# SUB-UNIT.net
KiCad netlist of a schematic drawn in EAGLE
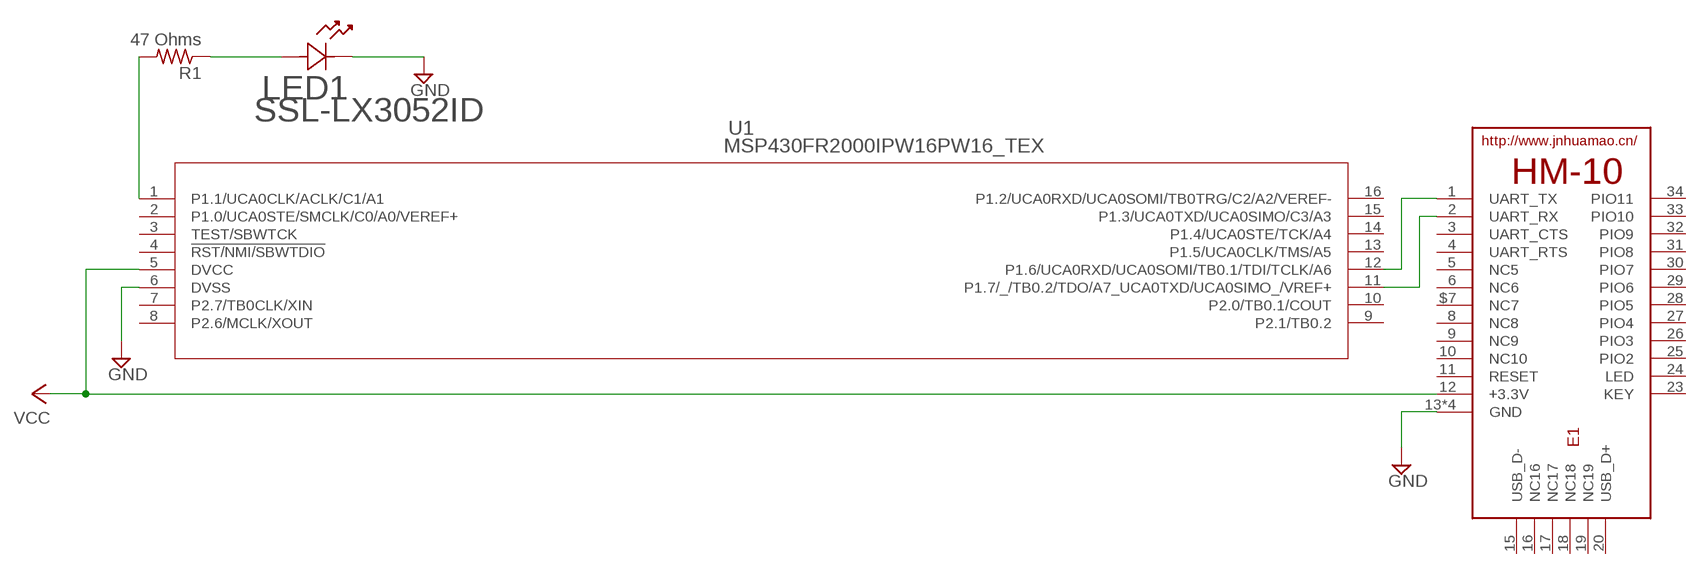
[diagram p0: schematic, sheet 1]

(export (version "E")
  (design (tool "Eeschema 10.0.6"))
  (components
    (comp (ref "E1")
      (value "HM-10-BOARD")
      (footprint "eagle-import:26.9X13X2.2_BOARD")
      (fields (field (name "MF") "Jinan Huamao Technology") (field (name "MP") "HM-10"))
      (libsource (lib "eagle-import") (part "HM-10-BOARD"))
    )
    (comp (ref "LED1")
      (value "SSL-LX3052ID")
      (footprint "eagle-import:LED_SSL-LX30_T-3_LUM")
      (fields (field (name "COPYRIGHT") "Copyright (C) 2023 Ultra Librarian. All rights reserved."))
      (libsource (lib "eagle-import") (part "SSL-LX3052ID"))
    )
    (comp (ref "R1")
      (value "47 Ohms")
      (footprint "eagle-import:0204_5")
      (libsource (lib "eagle-import") (part "R-US_0204/5"))
    )
    (comp (ref "U1")
      (value "MSP430FR2000IPW16PW16_TEX")
      (footprint "eagle-import:PW16_TEX")
      (fields
        (field (name "MANUFACTURER_PART_NUMBER") "MSP430FR2000IPW16")
        (field (name "COPYRIGHT") "Copyright (C) 2023 Ultra Librarian. All rights reserved.")
      )
      (libsource (lib "eagle-import") (part "MSP430FR2000IPW16PW16_TEX"))
    )
  )
  (nets
    (net (code "1") (name "GND") (class "Default")
      (node (ref "E1") (pin "13") (pinfunction "GND_13") (pintype "bidirectional"))
      (node (ref "E1") (pin "14") (pinfunction "GND_14") (pintype "bidirectional"))
      (node (ref "E1") (pin "21") (pinfunction "GND_21") (pintype "bidirectional"))
      (node (ref "E1") (pin "22") (pinfunction "GND_22") (pintype "bidirectional"))
      (node (ref "LED1") (pin "1") (pinfunction "ANODE_1") (pintype "passive"))
      (node (ref "U1") (pin "6") (pinfunction "DVSS_6") (pintype "power_in"))
    )
    (net (code "2") (name "Net-(E1-UART_RX)") (class "Default")
      (node (ref "E1") (pin "2") (pinfunction "UART_RX_2") (pintype "bidirectional"))
      (node (ref "U1") (pin "11") (pinfunction "P1.7/_/TB0.2/TDO/A7_UCA0TXD/UCA0SIMO_/VREF+_11") (pintype "bidirectional"))
    )
    (net (code "3") (name "Net-(E1-UART_TX)") (class "Default")
      (node (ref "E1") (pin "1") (pinfunction "UART_TX_1") (pintype "bidirectional"))
      (node (ref "U1") (pin "12") (pinfunction "P1.6/UCA0RXD/UCA0SOMI/TB0.1/TDI/TCLK/A6_12") (pintype "bidirectional"))
    )
    (net (code "4") (name "Net-(LED1-Pad2)") (class "Default")
      (node (ref "LED1") (pin "2") (pinfunction "2_2") (pintype "passive"))
      (node (ref "R1") (pin "1") (pinfunction "1_1") (pintype "passive"))
    )
    (net (code "5") (name "Net-(U1-P1.1{slash}UCA0CLK{slash}ACLK{slash}C1{slash}A1)") (class "Default")
      (node (ref "R1") (pin "2") (pinfunction "2_2") (pintype "passive"))
      (node (ref "U1") (pin "1") (pinfunction "P1.1/UCA0CLK/ACLK/C1/A1_1") (pintype "bidirectional"))
    )
    (net (code "6") (name "VCC") (class "Default")
      (node (ref "E1") (pin "12") (pinfunction "+3.3V_12") (pintype "bidirectional"))
      (node (ref "U1") (pin "5") (pinfunction "DVCC_5") (pintype "power_in"))
    )
    (net (code "7") (name "unconnected-(E1-KEY-Pad23)") (class "Default")
      (node (ref "E1") (pin "23") (pinfunction "KEY_23") (pintype "bidirectional"))
    )
    (net (code "8") (name "unconnected-(E1-LED-Pad24)") (class "Default")
      (node (ref "E1") (pin "24") (pinfunction "LED_24") (pintype "bidirectional"))
    )
    (net (code "9") (name "unconnected-(E1-NC5-Pad5)") (class "Default")
      (node (ref "E1") (pin "5") (pinfunction "NC5_5") (pintype "bidirectional"))
    )
    (net (code "10") (name "unconnected-(E1-NC6-Pad6)") (class "Default")
      (node (ref "E1") (pin "6") (pinfunction "NC6_6") (pintype "bidirectional"))
    )
    (net (code "11") (name "unconnected-(E1-NC7-Pad$7)") (class "Default")
      (node (ref "E1") (pin "$7") (pinfunction "NC7_$7") (pintype "bidirectional"))
    )
    (net (code "12") (name "unconnected-(E1-NC8-Pad8)") (class "Default")
      (node (ref "E1") (pin "8") (pinfunction "NC8_8") (pintype "bidirectional"))
    )
    (net (code "13") (name "unconnected-(E1-NC9-Pad9)") (class "Default")
      (node (ref "E1") (pin "9") (pinfunction "NC9_9") (pintype "bidirectional"))
    )
    (net (code "14") (name "unconnected-(E1-NC10-Pad10)") (class "Default")
      (node (ref "E1") (pin "10") (pinfunction "NC10_10") (pintype "bidirectional"))
    )
    (net (code "15") (name "unconnected-(E1-NC16-Pad16)") (class "Default")
      (node (ref "E1") (pin "16") (pinfunction "NC16_16") (pintype "bidirectional"))
    )
    (net (code "16") (name "unconnected-(E1-NC17-Pad17)") (class "Default")
      (node (ref "E1") (pin "17") (pinfunction "NC17_17") (pintype "bidirectional"))
    )
    (net (code "17") (name "unconnected-(E1-NC18-Pad18)") (class "Default")
      (node (ref "E1") (pin "18") (pinfunction "NC18_18") (pintype "bidirectional"))
    )
    (net (code "18") (name "unconnected-(E1-NC19-Pad19)") (class "Default")
      (node (ref "E1") (pin "19") (pinfunction "NC19_19") (pintype "bidirectional"))
    )
    (net (code "19") (name "unconnected-(E1-PIO2-Pad25)") (class "Default")
      (node (ref "E1") (pin "25") (pinfunction "PIO2_25") (pintype "bidirectional"))
    )
    (net (code "20") (name "unconnected-(E1-PIO3-Pad26)") (class "Default")
      (node (ref "E1") (pin "26") (pinfunction "PIO3_26") (pintype "bidirectional"))
    )
    (net (code "21") (name "unconnected-(E1-PIO4-Pad27)") (class "Default")
      (node (ref "E1") (pin "27") (pinfunction "PIO4_27") (pintype "bidirectional"))
    )
    (net (code "22") (name "unconnected-(E1-PIO5-Pad28)") (class "Default")
      (node (ref "E1") (pin "28") (pinfunction "PIO5_28") (pintype "bidirectional"))
    )
    (net (code "23") (name "unconnected-(E1-PIO6-Pad29)") (class "Default")
      (node (ref "E1") (pin "29") (pinfunction "PIO6_29") (pintype "bidirectional"))
    )
    (net (code "24") (name "unconnected-(E1-PIO7-Pad30)") (class "Default")
      (node (ref "E1") (pin "30") (pinfunction "PIO7_30") (pintype "bidirectional"))
    )
    (net (code "25") (name "unconnected-(E1-PIO8-Pad31)") (class "Default")
      (node (ref "E1") (pin "31") (pinfunction "PIO8_31") (pintype "bidirectional"))
    )
    (net (code "26") (name "unconnected-(E1-PIO9-Pad32)") (class "Default")
      (node (ref "E1") (pin "32") (pinfunction "PIO9_32") (pintype "bidirectional"))
    )
    (net (code "27") (name "unconnected-(E1-PIO10-Pad33)") (class "Default")
      (node (ref "E1") (pin "33") (pinfunction "PIO10_33") (pintype "bidirectional"))
    )
    (net (code "28") (name "unconnected-(E1-PIO11-Pad34)") (class "Default")
      (node (ref "E1") (pin "34") (pinfunction "PIO11_34") (pintype "bidirectional"))
    )
    (net (code "29") (name "unconnected-(E1-RESET-Pad11)") (class "Default")
      (node (ref "E1") (pin "11") (pinfunction "RESET_11") (pintype "bidirectional"))
    )
    (net (code "30") (name "unconnected-(E1-UART_CTS-Pad3)") (class "Default")
      (node (ref "E1") (pin "3") (pinfunction "UART_CTS_3") (pintype "bidirectional"))
    )
    (net (code "31") (name "unconnected-(E1-UART_RTS-Pad4)") (class "Default")
      (node (ref "E1") (pin "4") (pinfunction "UART_RTS_4") (pintype "bidirectional"))
    )
    (net (code "32") (name "unconnected-(E1-USB_D+-Pad20)") (class "Default")
      (node (ref "E1") (pin "20") (pinfunction "USB_D+_20") (pintype "bidirectional"))
    )
    (net (code "33") (name "unconnected-(E1-USB_D--Pad15)") (class "Default")
      (node (ref "E1") (pin "15") (pinfunction "USB_D-_15") (pintype "bidirectional"))
    )
    (net (code "34") (name "unconnected-(U1-P1.0{slash}UCA0STE{slash}SMCLK{slash}C0{slash}A0{slash}VEREF+-Pad2)") (class "Default")
      (node (ref "U1") (pin "2") (pinfunction "P1.0/UCA0STE/SMCLK/C0/A0/VEREF+_2") (pintype "bidirectional"))
    )
    (net (code "35") (name "unconnected-(U1-P1.2{slash}UCA0RXD{slash}UCA0SOMI{slash}TB0TRG{slash}C2{slash}A2{slash}VEREF--Pad16)") (class "Default")
      (node (ref "U1") (pin "16") (pinfunction "P1.2/UCA0RXD/UCA0SOMI/TB0TRG/C2/A2/VEREF-_16") (pintype "bidirectional"))
    )
    (net (code "36") (name "unconnected-(U1-P1.3{slash}UCA0TXD{slash}UCA0SIMO{slash}C3{slash}A3-Pad15)") (class "Default")
      (node (ref "U1") (pin "15") (pinfunction "P1.3/UCA0TXD/UCA0SIMO/C3/A3_15") (pintype "bidirectional"))
    )
    (net (code "37") (name "unconnected-(U1-P1.4{slash}UCA0STE{slash}TCK{slash}A4-Pad14)") (class "Default")
      (node (ref "U1") (pin "14") (pinfunction "P1.4/UCA0STE/TCK/A4_14") (pintype "bidirectional"))
    )
    (net (code "38") (name "unconnected-(U1-P1.5{slash}UCA0CLK{slash}TMS{slash}A5-Pad13)") (class "Default")
      (node (ref "U1") (pin "13") (pinfunction "P1.5/UCA0CLK/TMS/A5_13") (pintype "bidirectional"))
    )
    (net (code "39") (name "unconnected-(U1-P2.0{slash}TB0.1{slash}COUT-Pad10)") (class "Default")
      (node (ref "U1") (pin "10") (pinfunction "P2.0/TB0.1/COUT_10") (pintype "bidirectional"))
    )
    (net (code "40") (name "unconnected-(U1-P2.1{slash}TB0.2-Pad9)") (class "Default")
      (node (ref "U1") (pin "9") (pinfunction "P2.1/TB0.2_9") (pintype "bidirectional"))
    )
    (net (code "41") (name "unconnected-(U1-P2.6{slash}MCLK{slash}XOUT-Pad8)") (class "Default")
      (node (ref "U1") (pin "8") (pinfunction "P2.6/MCLK/XOUT_8") (pintype "bidirectional"))
    )
    (net (code "42") (name "unconnected-(U1-P2.7{slash}TB0CLK{slash}XIN-Pad7)") (class "Default")
      (node (ref "U1") (pin "7") (pinfunction "P2.7/TB0CLK/XIN_7") (pintype "bidirectional"))
    )
    (net (code "43") (name "unconnected-(U1-TEST{slash}SBWTCK-Pad3)") (class "Default")
      (node (ref "U1") (pin "3") (pinfunction "TEST/SBWTCK_3") (pintype "bidirectional"))
    )
    (net (code "44") (name "unconnected-(U1-~{RST{slash}NMI{slash}SBWTDIO}-Pad4)") (class "Default")
      (node (ref "U1") (pin "4") (pinfunction "~{RST/NMI/SBWTDIO}_4") (pintype "bidirectional"))
    )
  )
)
